# daughter_v2.net
KiCad netlist of a schematic drawn in EAGLE
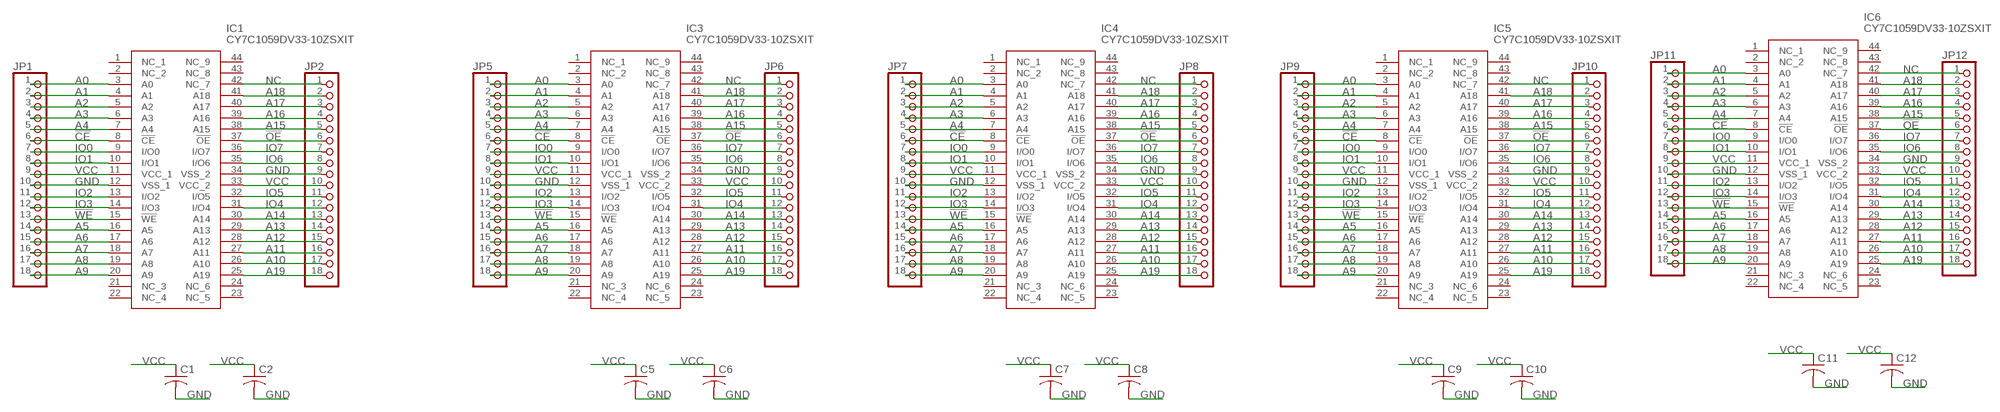
[diagram p0: schematic, sheet 1]

(export (version "E")
  (design (tool "Eeschema 10.0.6"))
  (components
    (comp (ref "C1")
      (value "C-USC0805")
      (footprint "eagle-import:C0805")
      (libsource (lib "eagle-import") (part "C-USC0805"))
    )
    (comp (ref "C2")
      (value "C-USC0805")
      (footprint "eagle-import:C0805")
      (libsource (lib "eagle-import") (part "C-USC0805"))
    )
    (comp (ref "C5")
      (value "C-USC0805")
      (footprint "eagle-import:C0805")
      (libsource (lib "eagle-import") (part "C-USC0805"))
    )
    (comp (ref "C6")
      (value "C-USC0805")
      (footprint "eagle-import:C0805")
      (libsource (lib "eagle-import") (part "C-USC0805"))
    )
    (comp (ref "C7")
      (value "C-USC0805")
      (footprint "eagle-import:C0805")
      (libsource (lib "eagle-import") (part "C-USC0805"))
    )
    (comp (ref "C8")
      (value "C-USC0805")
      (footprint "eagle-import:C0805")
      (libsource (lib "eagle-import") (part "C-USC0805"))
    )
    (comp (ref "C9")
      (value "C-USC0805")
      (footprint "eagle-import:C0805")
      (libsource (lib "eagle-import") (part "C-USC0805"))
    )
    (comp (ref "C10")
      (value "C-USC0805")
      (footprint "eagle-import:C0805")
      (libsource (lib "eagle-import") (part "C-USC0805"))
    )
    (comp (ref "C11")
      (value "C-USC0805")
      (footprint "eagle-import:C0805")
      (libsource (lib "eagle-import") (part "C-USC0805"))
    )
    (comp (ref "C12")
      (value "C-USC0805")
      (footprint "eagle-import:C0805")
      (libsource (lib "eagle-import") (part "C-USC0805"))
    )
    (comp (ref "IC1")
      (value "CY7C1059DV33-10ZSXIT")
      (footprint "eagle-import:SOP80P1184X119-44N")
      (fields (field (name "MOUSER_PART_NUMBER") "727-C1059DV3310ZSXIT"))
      (libsource (lib "eagle-import") (part "CY7C1059DV33-10ZSXIT"))
    )
    (comp (ref "IC3")
      (value "CY7C1059DV33-10ZSXIT")
      (footprint "eagle-import:SOP80P1184X119-44N")
      (fields (field (name "MOUSER_PART_NUMBER") "727-C1059DV3310ZSXIT"))
      (libsource (lib "eagle-import") (part "CY7C1059DV33-10ZSXIT"))
    )
    (comp (ref "IC4")
      (value "CY7C1059DV33-10ZSXIT")
      (footprint "eagle-import:SOP80P1184X119-44N")
      (fields (field (name "MOUSER_PART_NUMBER") "727-C1059DV3310ZSXIT"))
      (libsource (lib "eagle-import") (part "CY7C1059DV33-10ZSXIT"))
    )
    (comp (ref "IC5")
      (value "CY7C1059DV33-10ZSXIT")
      (footprint "eagle-import:SOP80P1184X119-44N")
      (fields (field (name "MOUSER_PART_NUMBER") "727-C1059DV3310ZSXIT"))
      (libsource (lib "eagle-import") (part "CY7C1059DV33-10ZSXIT"))
    )
    (comp (ref "IC6")
      (value "CY7C1059DV33-10ZSXIT")
      (footprint "eagle-import:SOP80P1184X119-44N")
      (fields (field (name "MOUSER_PART_NUMBER") "727-C1059DV3310ZSXIT"))
      (libsource (lib "eagle-import") (part "CY7C1059DV33-10ZSXIT"))
    )
    (comp (ref "JP1")
      (value "PINHD-1X18")
      (footprint "eagle-import:1X18")
      (libsource (lib "eagle-import") (part "PINHD-1X18"))
    )
    (comp (ref "JP2")
      (value "PINHD-1X18")
      (footprint "eagle-import:1X18")
      (libsource (lib "eagle-import") (part "PINHD-1X18"))
    )
    (comp (ref "JP5")
      (value "PINHD-1X18")
      (footprint "eagle-import:1X18")
      (libsource (lib "eagle-import") (part "PINHD-1X18"))
    )
    (comp (ref "JP6")
      (value "PINHD-1X18")
      (footprint "eagle-import:1X18")
      (libsource (lib "eagle-import") (part "PINHD-1X18"))
    )
    (comp (ref "JP7")
      (value "PINHD-1X18")
      (footprint "eagle-import:1X18")
      (libsource (lib "eagle-import") (part "PINHD-1X18"))
    )
    (comp (ref "JP8")
      (value "PINHD-1X18")
      (footprint "eagle-import:1X18")
      (libsource (lib "eagle-import") (part "PINHD-1X18"))
    )
    (comp (ref "JP9")
      (value "PINHD-1X18")
      (footprint "eagle-import:1X18")
      (libsource (lib "eagle-import") (part "PINHD-1X18"))
    )
    (comp (ref "JP10")
      (value "PINHD-1X18")
      (footprint "eagle-import:1X18")
      (libsource (lib "eagle-import") (part "PINHD-1X18"))
    )
    (comp (ref "JP11")
      (value "PINHD-1X18")
      (footprint "eagle-import:1X18")
      (libsource (lib "eagle-import") (part "PINHD-1X18"))
    )
    (comp (ref "JP12")
      (value "PINHD-1X18")
      (footprint "eagle-import:1X18")
      (libsource (lib "eagle-import") (part "PINHD-1X18"))
    )
  )
  (nets
    (net (code "1") (name "/A0") (class "Default")
      (node (ref "IC1") (pin "3") (pinfunction "A0_3") (pintype "bidirectional"))
      (node (ref "IC3") (pin "3") (pinfunction "A0_3") (pintype "bidirectional"))
      (node (ref "IC4") (pin "3") (pinfunction "A0_3") (pintype "bidirectional"))
      (node (ref "IC5") (pin "3") (pinfunction "A0_3") (pintype "bidirectional"))
      (node (ref "IC6") (pin "3") (pinfunction "A0_3") (pintype "bidirectional"))
      (node (ref "JP1") (pin "1") (pinfunction "1_1") (pintype "passive"))
      (node (ref "JP11") (pin "1") (pinfunction "1_1") (pintype "passive"))
      (node (ref "JP5") (pin "1") (pinfunction "1_1") (pintype "passive"))
      (node (ref "JP7") (pin "1") (pinfunction "1_1") (pintype "passive"))
      (node (ref "JP9") (pin "1") (pinfunction "1_1") (pintype "passive"))
    )
    (net (code "2") (name "/A1") (class "Default")
      (node (ref "IC1") (pin "4") (pinfunction "A1_4") (pintype "bidirectional"))
      (node (ref "IC3") (pin "4") (pinfunction "A1_4") (pintype "bidirectional"))
      (node (ref "IC4") (pin "4") (pinfunction "A1_4") (pintype "bidirectional"))
      (node (ref "IC5") (pin "4") (pinfunction "A1_4") (pintype "bidirectional"))
      (node (ref "IC6") (pin "4") (pinfunction "A1_4") (pintype "bidirectional"))
      (node (ref "JP1") (pin "2") (pinfunction "2_2") (pintype "passive"))
      (node (ref "JP11") (pin "2") (pinfunction "2_2") (pintype "passive"))
      (node (ref "JP5") (pin "2") (pinfunction "2_2") (pintype "passive"))
      (node (ref "JP7") (pin "2") (pinfunction "2_2") (pintype "passive"))
      (node (ref "JP9") (pin "2") (pinfunction "2_2") (pintype "passive"))
    )
    (net (code "3") (name "/A2") (class "Default")
      (node (ref "IC1") (pin "5") (pinfunction "A2_5") (pintype "bidirectional"))
      (node (ref "IC3") (pin "5") (pinfunction "A2_5") (pintype "bidirectional"))
      (node (ref "IC4") (pin "5") (pinfunction "A2_5") (pintype "bidirectional"))
      (node (ref "IC5") (pin "5") (pinfunction "A2_5") (pintype "bidirectional"))
      (node (ref "IC6") (pin "5") (pinfunction "A2_5") (pintype "bidirectional"))
      (node (ref "JP1") (pin "3") (pinfunction "3_3") (pintype "passive"))
      (node (ref "JP11") (pin "3") (pinfunction "3_3") (pintype "passive"))
      (node (ref "JP5") (pin "3") (pinfunction "3_3") (pintype "passive"))
      (node (ref "JP7") (pin "3") (pinfunction "3_3") (pintype "passive"))
      (node (ref "JP9") (pin "3") (pinfunction "3_3") (pintype "passive"))
    )
    (net (code "4") (name "/A3") (class "Default")
      (node (ref "IC1") (pin "6") (pinfunction "A3_6") (pintype "bidirectional"))
      (node (ref "IC3") (pin "6") (pinfunction "A3_6") (pintype "bidirectional"))
      (node (ref "IC4") (pin "6") (pinfunction "A3_6") (pintype "bidirectional"))
      (node (ref "IC5") (pin "6") (pinfunction "A3_6") (pintype "bidirectional"))
      (node (ref "IC6") (pin "6") (pinfunction "A3_6") (pintype "bidirectional"))
      (node (ref "JP1") (pin "4") (pinfunction "4_4") (pintype "passive"))
      (node (ref "JP11") (pin "4") (pinfunction "4_4") (pintype "passive"))
      (node (ref "JP5") (pin "4") (pinfunction "4_4") (pintype "passive"))
      (node (ref "JP7") (pin "4") (pinfunction "4_4") (pintype "passive"))
      (node (ref "JP9") (pin "4") (pinfunction "4_4") (pintype "passive"))
    )
    (net (code "5") (name "/A4") (class "Default")
      (node (ref "IC1") (pin "7") (pinfunction "A4_7") (pintype "bidirectional"))
      (node (ref "IC3") (pin "7") (pinfunction "A4_7") (pintype "bidirectional"))
      (node (ref "IC4") (pin "7") (pinfunction "A4_7") (pintype "bidirectional"))
      (node (ref "IC5") (pin "7") (pinfunction "A4_7") (pintype "bidirectional"))
      (node (ref "IC6") (pin "7") (pinfunction "A4_7") (pintype "bidirectional"))
      (node (ref "JP1") (pin "5") (pinfunction "5_5") (pintype "passive"))
      (node (ref "JP11") (pin "5") (pinfunction "5_5") (pintype "passive"))
      (node (ref "JP5") (pin "5") (pinfunction "5_5") (pintype "passive"))
      (node (ref "JP7") (pin "5") (pinfunction "5_5") (pintype "passive"))
      (node (ref "JP9") (pin "5") (pinfunction "5_5") (pintype "passive"))
    )
    (net (code "6") (name "/A5") (class "Default")
      (node (ref "IC1") (pin "16") (pinfunction "A5_16") (pintype "bidirectional"))
      (node (ref "IC3") (pin "16") (pinfunction "A5_16") (pintype "bidirectional"))
      (node (ref "IC4") (pin "16") (pinfunction "A5_16") (pintype "bidirectional"))
      (node (ref "IC5") (pin "16") (pinfunction "A5_16") (pintype "bidirectional"))
      (node (ref "IC6") (pin "16") (pinfunction "A5_16") (pintype "bidirectional"))
      (node (ref "JP1") (pin "14") (pinfunction "14_14") (pintype "passive"))
      (node (ref "JP11") (pin "14") (pinfunction "14_14") (pintype "passive"))
      (node (ref "JP5") (pin "14") (pinfunction "14_14") (pintype "passive"))
      (node (ref "JP7") (pin "14") (pinfunction "14_14") (pintype "passive"))
      (node (ref "JP9") (pin "14") (pinfunction "14_14") (pintype "passive"))
    )
    (net (code "7") (name "/A6") (class "Default")
      (node (ref "IC1") (pin "17") (pinfunction "A6_17") (pintype "bidirectional"))
      (node (ref "IC3") (pin "17") (pinfunction "A6_17") (pintype "bidirectional"))
      (node (ref "IC4") (pin "17") (pinfunction "A6_17") (pintype "bidirectional"))
      (node (ref "IC5") (pin "17") (pinfunction "A6_17") (pintype "bidirectional"))
      (node (ref "IC6") (pin "17") (pinfunction "A6_17") (pintype "bidirectional"))
      (node (ref "JP1") (pin "15") (pinfunction "15_15") (pintype "passive"))
      (node (ref "JP11") (pin "15") (pinfunction "15_15") (pintype "passive"))
      (node (ref "JP5") (pin "15") (pinfunction "15_15") (pintype "passive"))
      (node (ref "JP7") (pin "15") (pinfunction "15_15") (pintype "passive"))
      (node (ref "JP9") (pin "15") (pinfunction "15_15") (pintype "passive"))
    )
    (net (code "8") (name "/A7") (class "Default")
      (node (ref "IC1") (pin "18") (pinfunction "A7_18") (pintype "bidirectional"))
      (node (ref "IC3") (pin "18") (pinfunction "A7_18") (pintype "bidirectional"))
      (node (ref "IC4") (pin "18") (pinfunction "A7_18") (pintype "bidirectional"))
      (node (ref "IC5") (pin "18") (pinfunction "A7_18") (pintype "bidirectional"))
      (node (ref "IC6") (pin "18") (pinfunction "A7_18") (pintype "bidirectional"))
      (node (ref "JP1") (pin "16") (pinfunction "16_16") (pintype "passive"))
      (node (ref "JP11") (pin "16") (pinfunction "16_16") (pintype "passive"))
      (node (ref "JP5") (pin "16") (pinfunction "16_16") (pintype "passive"))
      (node (ref "JP7") (pin "16") (pinfunction "16_16") (pintype "passive"))
      (node (ref "JP9") (pin "16") (pinfunction "16_16") (pintype "passive"))
    )
    (net (code "9") (name "/A8") (class "Default")
      (node (ref "IC1") (pin "19") (pinfunction "A8_19") (pintype "bidirectional"))
      (node (ref "IC3") (pin "19") (pinfunction "A8_19") (pintype "bidirectional"))
      (node (ref "IC4") (pin "19") (pinfunction "A8_19") (pintype "bidirectional"))
      (node (ref "IC5") (pin "19") (pinfunction "A8_19") (pintype "bidirectional"))
      (node (ref "IC6") (pin "19") (pinfunction "A8_19") (pintype "bidirectional"))
      (node (ref "JP1") (pin "17") (pinfunction "17_17") (pintype "passive"))
      (node (ref "JP11") (pin "17") (pinfunction "17_17") (pintype "passive"))
      (node (ref "JP5") (pin "17") (pinfunction "17_17") (pintype "passive"))
      (node (ref "JP7") (pin "17") (pinfunction "17_17") (pintype "passive"))
      (node (ref "JP9") (pin "17") (pinfunction "17_17") (pintype "passive"))
    )
    (net (code "10") (name "/A9") (class "Default")
      (node (ref "IC1") (pin "20") (pinfunction "A9_20") (pintype "bidirectional"))
      (node (ref "IC3") (pin "20") (pinfunction "A9_20") (pintype "bidirectional"))
      (node (ref "IC4") (pin "20") (pinfunction "A9_20") (pintype "bidirectional"))
      (node (ref "IC5") (pin "20") (pinfunction "A9_20") (pintype "bidirectional"))
      (node (ref "IC6") (pin "20") (pinfunction "A9_20") (pintype "bidirectional"))
      (node (ref "JP1") (pin "18") (pinfunction "18_18") (pintype "passive"))
      (node (ref "JP11") (pin "18") (pinfunction "18_18") (pintype "passive"))
      (node (ref "JP5") (pin "18") (pinfunction "18_18") (pintype "passive"))
      (node (ref "JP7") (pin "18") (pinfunction "18_18") (pintype "passive"))
      (node (ref "JP9") (pin "18") (pinfunction "18_18") (pintype "passive"))
    )
    (net (code "11") (name "/A10") (class "Default")
      (node (ref "IC1") (pin "26") (pinfunction "A10_26") (pintype "bidirectional"))
      (node (ref "IC3") (pin "26") (pinfunction "A10_26") (pintype "bidirectional"))
      (node (ref "IC4") (pin "26") (pinfunction "A10_26") (pintype "bidirectional"))
      (node (ref "IC5") (pin "26") (pinfunction "A10_26") (pintype "bidirectional"))
      (node (ref "IC6") (pin "26") (pinfunction "A10_26") (pintype "bidirectional"))
      (node (ref "JP10") (pin "17") (pinfunction "17_17") (pintype "passive"))
      (node (ref "JP12") (pin "17") (pinfunction "17_17") (pintype "passive"))
      (node (ref "JP2") (pin "17") (pinfunction "17_17") (pintype "passive"))
      (node (ref "JP6") (pin "17") (pinfunction "17_17") (pintype "passive"))
      (node (ref "JP8") (pin "17") (pinfunction "17_17") (pintype "passive"))
    )
    (net (code "12") (name "/A11") (class "Default")
      (node (ref "IC1") (pin "27") (pinfunction "A11_27") (pintype "bidirectional"))
      (node (ref "IC3") (pin "27") (pinfunction "A11_27") (pintype "bidirectional"))
      (node (ref "IC4") (pin "27") (pinfunction "A11_27") (pintype "bidirectional"))
      (node (ref "IC5") (pin "27") (pinfunction "A11_27") (pintype "bidirectional"))
      (node (ref "IC6") (pin "27") (pinfunction "A11_27") (pintype "bidirectional"))
      (node (ref "JP10") (pin "16") (pinfunction "16_16") (pintype "passive"))
      (node (ref "JP12") (pin "16") (pinfunction "16_16") (pintype "passive"))
      (node (ref "JP2") (pin "16") (pinfunction "16_16") (pintype "passive"))
      (node (ref "JP6") (pin "16") (pinfunction "16_16") (pintype "passive"))
      (node (ref "JP8") (pin "16") (pinfunction "16_16") (pintype "passive"))
    )
    (net (code "13") (name "/A12") (class "Default")
      (node (ref "IC1") (pin "28") (pinfunction "A12_28") (pintype "bidirectional"))
      (node (ref "IC3") (pin "28") (pinfunction "A12_28") (pintype "bidirectional"))
      (node (ref "IC4") (pin "28") (pinfunction "A12_28") (pintype "bidirectional"))
      (node (ref "IC5") (pin "28") (pinfunction "A12_28") (pintype "bidirectional"))
      (node (ref "IC6") (pin "28") (pinfunction "A12_28") (pintype "bidirectional"))
      (node (ref "JP10") (pin "15") (pinfunction "15_15") (pintype "passive"))
      (node (ref "JP12") (pin "15") (pinfunction "15_15") (pintype "passive"))
      (node (ref "JP2") (pin "15") (pinfunction "15_15") (pintype "passive"))
      (node (ref "JP6") (pin "15") (pinfunction "15_15") (pintype "passive"))
      (node (ref "JP8") (pin "15") (pinfunction "15_15") (pintype "passive"))
    )
    (net (code "14") (name "/A13") (class "Default")
      (node (ref "IC1") (pin "29") (pinfunction "A13_29") (pintype "bidirectional"))
      (node (ref "IC3") (pin "29") (pinfunction "A13_29") (pintype "bidirectional"))
      (node (ref "IC4") (pin "29") (pinfunction "A13_29") (pintype "bidirectional"))
      (node (ref "IC5") (pin "29") (pinfunction "A13_29") (pintype "bidirectional"))
      (node (ref "IC6") (pin "29") (pinfunction "A13_29") (pintype "bidirectional"))
      (node (ref "JP10") (pin "14") (pinfunction "14_14") (pintype "passive"))
      (node (ref "JP12") (pin "14") (pinfunction "14_14") (pintype "passive"))
      (node (ref "JP2") (pin "14") (pinfunction "14_14") (pintype "passive"))
      (node (ref "JP6") (pin "14") (pinfunction "14_14") (pintype "passive"))
      (node (ref "JP8") (pin "14") (pinfunction "14_14") (pintype "passive"))
    )
    (net (code "15") (name "/A14") (class "Default")
      (node (ref "IC1") (pin "30") (pinfunction "A14_30") (pintype "bidirectional"))
      (node (ref "IC3") (pin "30") (pinfunction "A14_30") (pintype "bidirectional"))
      (node (ref "IC4") (pin "30") (pinfunction "A14_30") (pintype "bidirectional"))
      (node (ref "IC5") (pin "30") (pinfunction "A14_30") (pintype "bidirectional"))
      (node (ref "IC6") (pin "30") (pinfunction "A14_30") (pintype "bidirectional"))
      (node (ref "JP10") (pin "13") (pinfunction "13_13") (pintype "passive"))
      (node (ref "JP12") (pin "13") (pinfunction "13_13") (pintype "passive"))
      (node (ref "JP2") (pin "13") (pinfunction "13_13") (pintype "passive"))
      (node (ref "JP6") (pin "13") (pinfunction "13_13") (pintype "passive"))
      (node (ref "JP8") (pin "13") (pinfunction "13_13") (pintype "passive"))
    )
    (net (code "16") (name "/A15") (class "Default")
      (node (ref "IC1") (pin "38") (pinfunction "A15_38") (pintype "bidirectional"))
      (node (ref "IC3") (pin "38") (pinfunction "A15_38") (pintype "bidirectional"))
      (node (ref "IC4") (pin "38") (pinfunction "A15_38") (pintype "bidirectional"))
      (node (ref "IC5") (pin "38") (pinfunction "A15_38") (pintype "bidirectional"))
      (node (ref "IC6") (pin "38") (pinfunction "A15_38") (pintype "bidirectional"))
      (node (ref "JP10") (pin "5") (pinfunction "5_5") (pintype "passive"))
      (node (ref "JP12") (pin "5") (pinfunction "5_5") (pintype "passive"))
      (node (ref "JP2") (pin "5") (pinfunction "5_5") (pintype "passive"))
      (node (ref "JP6") (pin "5") (pinfunction "5_5") (pintype "passive"))
      (node (ref "JP8") (pin "5") (pinfunction "5_5") (pintype "passive"))
    )
    (net (code "17") (name "/A16") (class "Default")
      (node (ref "IC1") (pin "39") (pinfunction "A16_39") (pintype "bidirectional"))
      (node (ref "IC3") (pin "39") (pinfunction "A16_39") (pintype "bidirectional"))
      (node (ref "IC4") (pin "39") (pinfunction "A16_39") (pintype "bidirectional"))
      (node (ref "IC5") (pin "39") (pinfunction "A16_39") (pintype "bidirectional"))
      (node (ref "IC6") (pin "39") (pinfunction "A16_39") (pintype "bidirectional"))
      (node (ref "JP10") (pin "4") (pinfunction "4_4") (pintype "passive"))
      (node (ref "JP12") (pin "4") (pinfunction "4_4") (pintype "passive"))
      (node (ref "JP2") (pin "4") (pinfunction "4_4") (pintype "passive"))
      (node (ref "JP6") (pin "4") (pinfunction "4_4") (pintype "passive"))
      (node (ref "JP8") (pin "4") (pinfunction "4_4") (pintype "passive"))
    )
    (net (code "18") (name "/A17") (class "Default")
      (node (ref "IC1") (pin "40") (pinfunction "A17_40") (pintype "bidirectional"))
      (node (ref "IC3") (pin "40") (pinfunction "A17_40") (pintype "bidirectional"))
      (node (ref "IC4") (pin "40") (pinfunction "A17_40") (pintype "bidirectional"))
      (node (ref "IC5") (pin "40") (pinfunction "A17_40") (pintype "bidirectional"))
      (node (ref "IC6") (pin "40") (pinfunction "A17_40") (pintype "bidirectional"))
      (node (ref "JP10") (pin "3") (pinfunction "3_3") (pintype "passive"))
      (node (ref "JP12") (pin "3") (pinfunction "3_3") (pintype "passive"))
      (node (ref "JP2") (pin "3") (pinfunction "3_3") (pintype "passive"))
      (node (ref "JP6") (pin "3") (pinfunction "3_3") (pintype "passive"))
      (node (ref "JP8") (pin "3") (pinfunction "3_3") (pintype "passive"))
    )
    (net (code "19") (name "/A18") (class "Default")
      (node (ref "IC1") (pin "41") (pinfunction "A18_41") (pintype "bidirectional"))
      (node (ref "IC3") (pin "41") (pinfunction "A18_41") (pintype "bidirectional"))
      (node (ref "IC4") (pin "41") (pinfunction "A18_41") (pintype "bidirectional"))
      (node (ref "IC5") (pin "41") (pinfunction "A18_41") (pintype "bidirectional"))
      (node (ref "IC6") (pin "41") (pinfunction "A18_41") (pintype "bidirectional"))
      (node (ref "JP10") (pin "2") (pinfunction "2_2") (pintype "passive"))
      (node (ref "JP12") (pin "2") (pinfunction "2_2") (pintype "passive"))
      (node (ref "JP2") (pin "2") (pinfunction "2_2") (pintype "passive"))
      (node (ref "JP6") (pin "2") (pinfunction "2_2") (pintype "passive"))
      (node (ref "JP8") (pin "2") (pinfunction "2_2") (pintype "passive"))
    )
    (net (code "20") (name "/A19") (class "Default")
      (node (ref "IC1") (pin "25") (pinfunction "A19_25") (pintype "bidirectional"))
      (node (ref "IC3") (pin "25") (pinfunction "A19_25") (pintype "bidirectional"))
      (node (ref "IC4") (pin "25") (pinfunction "A19_25") (pintype "bidirectional"))
      (node (ref "IC5") (pin "25") (pinfunction "A19_25") (pintype "bidirectional"))
      (node (ref "IC6") (pin "25") (pinfunction "A19_25") (pintype "bidirectional"))
      (node (ref "JP10") (pin "18") (pinfunction "18_18") (pintype "passive"))
      (node (ref "JP12") (pin "18") (pinfunction "18_18") (pintype "passive"))
      (node (ref "JP2") (pin "18") (pinfunction "18_18") (pintype "passive"))
      (node (ref "JP6") (pin "18") (pinfunction "18_18") (pintype "passive"))
      (node (ref "JP8") (pin "18") (pinfunction "18_18") (pintype "passive"))
    )
    (net (code "21") (name "/GND") (class "Default")
      (node (ref "C1") (pin "2") (pinfunction "2_2") (pintype "passive"))
      (node (ref "C10") (pin "2") (pinfunction "2_2") (pintype "passive"))
      (node (ref "C11") (pin "2") (pinfunction "2_2") (pintype "passive"))
      (node (ref "C12") (pin "2") (pinfunction "2_2") (pintype "passive"))
      (node (ref "C2") (pin "2") (pinfunction "2_2") (pintype "passive"))
      (node (ref "C5") (pin "2") (pinfunction "2_2") (pintype "passive"))
      (node (ref "C6") (pin "2") (pinfunction "2_2") (pintype "passive"))
      (node (ref "C7") (pin "2") (pinfunction "2_2") (pintype "passive"))
      (node (ref "C8") (pin "2") (pinfunction "2_2") (pintype "passive"))
      (node (ref "C9") (pin "2") (pinfunction "2_2") (pintype "passive"))
      (node (ref "IC1") (pin "12") (pinfunction "VSS_1_12") (pintype "bidirectional"))
      (node (ref "IC1") (pin "34") (pinfunction "VSS_2_34") (pintype "bidirectional"))
      (node (ref "IC3") (pin "12") (pinfunction "VSS_1_12") (pintype "bidirectional"))
      (node (ref "IC3") (pin "34") (pinfunction "VSS_2_34") (pintype "bidirectional"))
      (node (ref "IC4") (pin "12") (pinfunction "VSS_1_12") (pintype "bidirectional"))
      (node (ref "IC4") (pin "34") (pinfunction "VSS_2_34") (pintype "bidirectional"))
      (node (ref "IC5") (pin "12") (pinfunction "VSS_1_12") (pintype "bidirectional"))
      (node (ref "IC5") (pin "34") (pinfunction "VSS_2_34") (pintype "bidirectional"))
      (node (ref "IC6") (pin "12") (pinfunction "VSS_1_12") (pintype "bidirectional"))
      (node (ref "IC6") (pin "34") (pinfunction "VSS_2_34") (pintype "bidirectional"))
      (node (ref "JP1") (pin "10") (pinfunction "10_10") (pintype "passive"))
      (node (ref "JP10") (pin "9") (pinfunction "9_9") (pintype "passive"))
      (node (ref "JP11") (pin "10") (pinfunction "10_10") (pintype "passive"))
      (node (ref "JP12") (pin "9") (pinfunction "9_9") (pintype "passive"))
      (node (ref "JP2") (pin "9") (pinfunction "9_9") (pintype "passive"))
      (node (ref "JP5") (pin "10") (pinfunction "10_10") (pintype "passive"))
      (node (ref "JP6") (pin "9") (pinfunction "9_9") (pintype "passive"))
      (node (ref "JP7") (pin "10") (pinfunction "10_10") (pintype "passive"))
      (node (ref "JP8") (pin "9") (pinfunction "9_9") (pintype "passive"))
      (node (ref "JP9") (pin "10") (pinfunction "10_10") (pintype "passive"))
    )
    (net (code "22") (name "/IO0") (class "Default")
      (node (ref "IC1") (pin "9") (pinfunction "I/O0_9") (pintype "bidirectional"))
      (node (ref "IC3") (pin "9") (pinfunction "I/O0_9") (pintype "bidirectional"))
      (node (ref "IC4") (pin "9") (pinfunction "I/O0_9") (pintype "bidirectional"))
      (node (ref "IC5") (pin "9") (pinfunction "I/O0_9") (pintype "bidirectional"))
      (node (ref "IC6") (pin "9") (pinfunction "I/O0_9") (pintype "bidirectional"))
      (node (ref "JP1") (pin "7") (pinfunction "7_7") (pintype "passive"))
      (node (ref "JP11") (pin "7") (pinfunction "7_7") (pintype "passive"))
      (node (ref "JP5") (pin "7") (pinfunction "7_7") (pintype "passive"))
      (node (ref "JP7") (pin "7") (pinfunction "7_7") (pintype "passive"))
      (node (ref "JP9") (pin "7") (pinfunction "7_7") (pintype "passive"))
    )
    (net (code "23") (name "/IO1") (class "Default")
      (node (ref "IC1") (pin "10") (pinfunction "I/O1_10") (pintype "bidirectional"))
      (node (ref "IC3") (pin "10") (pinfunction "I/O1_10") (pintype "bidirectional"))
      (node (ref "IC4") (pin "10") (pinfunction "I/O1_10") (pintype "bidirectional"))
      (node (ref "IC5") (pin "10") (pinfunction "I/O1_10") (pintype "bidirectional"))
      (node (ref "IC6") (pin "10") (pinfunction "I/O1_10") (pintype "bidirectional"))
      (node (ref "JP1") (pin "8") (pinfunction "8_8") (pintype "passive"))
      (node (ref "JP11") (pin "8") (pinfunction "8_8") (pintype "passive"))
      (node (ref "JP5") (pin "8") (pinfunction "8_8") (pintype "passive"))
      (node (ref "JP7") (pin "8") (pinfunction "8_8") (pintype "passive"))
      (node (ref "JP9") (pin "8") (pinfunction "8_8") (pintype "passive"))
    )
    (net (code "24") (name "/IO2") (class "Default")
      (node (ref "IC1") (pin "13") (pinfunction "I/O2_13") (pintype "bidirectional"))
      (node (ref "IC3") (pin "13") (pinfunction "I/O2_13") (pintype "bidirectional"))
      (node (ref "IC4") (pin "13") (pinfunction "I/O2_13") (pintype "bidirectional"))
      (node (ref "IC5") (pin "13") (pinfunction "I/O2_13") (pintype "bidirectional"))
      (node (ref "IC6") (pin "13") (pinfunction "I/O2_13") (pintype "bidirectional"))
      (node (ref "JP1") (pin "11") (pinfunction "11_11") (pintype "passive"))
      (node (ref "JP11") (pin "11") (pinfunction "11_11") (pintype "passive"))
      (node (ref "JP5") (pin "11") (pinfunction "11_11") (pintype "passive"))
      (node (ref "JP7") (pin "11") (pinfunction "11_11") (pintype "passive"))
      (node (ref "JP9") (pin "11") (pinfunction "11_11") (pintype "passive"))
    )
    (net (code "25") (name "/IO3") (class "Default")
      (node (ref "IC1") (pin "14") (pinfunction "I/O3_14") (pintype "bidirectional"))
      (node (ref "IC3") (pin "14") (pinfunction "I/O3_14") (pintype "bidirectional"))
      (node (ref "IC4") (pin "14") (pinfunction "I/O3_14") (pintype "bidirectional"))
      (node (ref "IC5") (pin "14") (pinfunction "I/O3_14") (pintype "bidirectional"))
      (node (ref "IC6") (pin "14") (pinfunction "I/O3_14") (pintype "bidirectional"))
      (node (ref "JP1") (pin "12") (pinfunction "12_12") (pintype "passive"))
      (node (ref "JP11") (pin "12") (pinfunction "12_12") (pintype "passive"))
      (node (ref "JP5") (pin "12") (pinfunction "12_12") (pintype "passive"))
      (node (ref "JP7") (pin "12") (pinfunction "12_12") (pintype "passive"))
      (node (ref "JP9") (pin "12") (pinfunction "12_12") (pintype "passive"))
    )
    (net (code "26") (name "/IO4") (class "Default")
      (node (ref "IC1") (pin "31") (pinfunction "I/O4_31") (pintype "bidirectional"))
      (node (ref "IC3") (pin "31") (pinfunction "I/O4_31") (pintype "bidirectional"))
      (node (ref "IC4") (pin "31") (pinfunction "I/O4_31") (pintype "bidirectional"))
      (node (ref "IC5") (pin "31") (pinfunction "I/O4_31") (pintype "bidirectional"))
      (node (ref "IC6") (pin "31") (pinfunction "I/O4_31") (pintype "bidirectional"))
      (node (ref "JP10") (pin "12") (pinfunction "12_12") (pintype "passive"))
      (node (ref "JP12") (pin "12") (pinfunction "12_12") (pintype "passive"))
      (node (ref "JP2") (pin "12") (pinfunction "12_12") (pintype "passive"))
      (node (ref "JP6") (pin "12") (pinfunction "12_12") (pintype "passive"))
      (node (ref "JP8") (pin "12") (pinfunction "12_12") (pintype "passive"))
    )
    (net (code "27") (name "/IO5") (class "Default")
      (node (ref "IC1") (pin "32") (pinfunction "I/O5_32") (pintype "bidirectional"))
      (node (ref "IC3") (pin "32") (pinfunction "I/O5_32") (pintype "bidirectional"))
      (node (ref "IC4") (pin "32") (pinfunction "I/O5_32") (pintype "bidirectional"))
      (node (ref "IC5") (pin "32") (pinfunction "I/O5_32") (pintype "bidirectional"))
      (node (ref "IC6") (pin "32") (pinfunction "I/O5_32") (pintype "bidirectional"))
      (node (ref "JP10") (pin "11") (pinfunction "11_11") (pintype "passive"))
      (node (ref "JP12") (pin "11") (pinfunction "11_11") (pintype "passive"))
      (node (ref "JP2") (pin "11") (pinfunction "11_11") (pintype "passive"))
      (node (ref "JP6") (pin "11") (pinfunction "11_11") (pintype "passive"))
      (node (ref "JP8") (pin "11") (pinfunction "11_11") (pintype "passive"))
    )
    (net (code "28") (name "/IO6") (class "Default")
      (node (ref "IC1") (pin "35") (pinfunction "I/O6_35") (pintype "bidirectional"))
      (node (ref "IC3") (pin "35") (pinfunction "I/O6_35") (pintype "bidirectional"))
      (node (ref "IC4") (pin "35") (pinfunction "I/O6_35") (pintype "bidirectional"))
      (node (ref "IC5") (pin "35") (pinfunction "I/O6_35") (pintype "bidirectional"))
      (node (ref "IC6") (pin "35") (pinfunction "I/O6_35") (pintype "bidirectional"))
      (node (ref "JP10") (pin "8") (pinfunction "8_8") (pintype "passive"))
      (node (ref "JP12") (pin "8") (pinfunction "8_8") (pintype "passive"))
      (node (ref "JP2") (pin "8") (pinfunction "8_8") (pintype "passive"))
      (node (ref "JP6") (pin "8") (pinfunction "8_8") (pintype "passive"))
      (node (ref "JP8") (pin "8") (pinfunction "8_8") (pintype "passive"))
    )
    (net (code "29") (name "/IO7") (class "Default")
      (node (ref "IC1") (pin "36") (pinfunction "I/O7_36") (pintype "bidirectional"))
      (node (ref "IC3") (pin "36") (pinfunction "I/O7_36") (pintype "bidirectional"))
      (node (ref "IC4") (pin "36") (pinfunction "I/O7_36") (pintype "bidirectional"))
      (node (ref "IC5") (pin "36") (pinfunction "I/O7_36") (pintype "bidirectional"))
      (node (ref "IC6") (pin "36") (pinfunction "I/O7_36") (pintype "bidirectional"))
      (node (ref "JP10") (pin "7") (pinfunction "7_7") (pintype "passive"))
      (node (ref "JP12") (pin "7") (pinfunction "7_7") (pintype "passive"))
      (node (ref "JP2") (pin "7") (pinfunction "7_7") (pintype "passive"))
      (node (ref "JP6") (pin "7") (pinfunction "7_7") (pintype "passive"))
      (node (ref "JP8") (pin "7") (pinfunction "7_7") (pintype "passive"))
    )
    (net (code "30") (name "/NC") (class "Default")
      (node (ref "IC1") (pin "42") (pinfunction "NC_7_42") (pintype "bidirectional"))
      (node (ref "IC3") (pin "42") (pinfunction "NC_7_42") (pintype "bidirectional"))
      (node (ref "IC4") (pin "42") (pinfunction "NC_7_42") (pintype "bidirectional"))
      (node (ref "IC5") (pin "42") (pinfunction "NC_7_42") (pintype "bidirectional"))
      (node (ref "IC6") (pin "42") (pinfunction "NC_7_42") (pintype "bidirectional"))
      (node (ref "JP10") (pin "1") (pinfunction "1_1") (pintype "passive"))
      (node (ref "JP12") (pin "1") (pinfunction "1_1") (pintype "passive"))
      (node (ref "JP2") (pin "1") (pinfunction "1_1") (pintype "passive"))
      (node (ref "JP6") (pin "1") (pinfunction "1_1") (pintype "passive"))
      (node (ref "JP8") (pin "1") (pinfunction "1_1") (pintype "passive"))
    )
    (net (code "31") (name "/VCC") (class "Default")
      (node (ref "C1") (pin "1") (pinfunction "1_1") (pintype "passive"))
      (node (ref "C10") (pin "1") (pinfunction "1_1") (pintype "passive"))
      (node (ref "C11") (pin "1") (pinfunction "1_1") (pintype "passive"))
      (node (ref "C12") (pin "1") (pinfunction "1_1") (pintype "passive"))
      (node (ref "C2") (pin "1") (pinfunction "1_1") (pintype "passive"))
      (node (ref "C5") (pin "1") (pinfunction "1_1") (pintype "passive"))
      (node (ref "C6") (pin "1") (pinfunction "1_1") (pintype "passive"))
      (node (ref "C7") (pin "1") (pinfunction "1_1") (pintype "passive"))
      (node (ref "C8") (pin "1") (pinfunction "1_1") (pintype "passive"))
      (node (ref "C9") (pin "1") (pinfunction "1_1") (pintype "passive"))
      (node (ref "IC1") (pin "11") (pinfunction "VCC_1_11") (pintype "bidirectional"))
      (node (ref "IC1") (pin "33") (pinfunction "VCC_2_33") (pintype "bidirectional"))
      (node (ref "IC3") (pin "11") (pinfunction "VCC_1_11") (pintype "bidirectional"))
      (node (ref "IC3") (pin "33") (pinfunction "VCC_2_33") (pintype "bidirectional"))
      (node (ref "IC4") (pin "11") (pinfunction "VCC_1_11") (pintype "bidirectional"))
      (node (ref "IC4") (pin "33") (pinfunction "VCC_2_33") (pintype "bidirectional"))
      (node (ref "IC5") (pin "11") (pinfunction "VCC_1_11") (pintype "bidirectional"))
      (node (ref "IC5") (pin "33") (pinfunction "VCC_2_33") (pintype "bidirectional"))
      (node (ref "IC6") (pin "11") (pinfunction "VCC_1_11") (pintype "bidirectional"))
      (node (ref "IC6") (pin "33") (pinfunction "VCC_2_33") (pintype "bidirectional"))
      (node (ref "JP1") (pin "9") (pinfunction "9_9") (pintype "passive"))
      (node (ref "JP10") (pin "10") (pinfunction "10_10") (pintype "passive"))
      (node (ref "JP11") (pin "9") (pinfunction "9_9") (pintype "passive"))
      (node (ref "JP12") (pin "10") (pinfunction "10_10") (pintype "passive"))
      (node (ref "JP2") (pin "10") (pinfunction "10_10") (pintype "passive"))
      (node (ref "JP5") (pin "9") (pinfunction "9_9") (pintype "passive"))
      (node (ref "JP6") (pin "10") (pinfunction "10_10") (pintype "passive"))
      (node (ref "JP7") (pin "9") (pinfunction "9_9") (pintype "passive"))
      (node (ref "JP8") (pin "10") (pinfunction "10_10") (pintype "passive"))
      (node (ref "JP9") (pin "9") (pinfunction "9_9") (pintype "passive"))
    )
    (net (code "32") (name "/~{CE}") (class "Default")
      (node (ref "IC1") (pin "8") (pinfunction "~{CE}_8") (pintype "bidirectional"))
      (node (ref "IC3") (pin "8") (pinfunction "~{CE}_8") (pintype "bidirectional"))
      (node (ref "IC4") (pin "8") (pinfunction "~{CE}_8") (pintype "bidirectional"))
      (node (ref "IC5") (pin "8") (pinfunction "~{CE}_8") (pintype "bidirectional"))
      (node (ref "IC6") (pin "8") (pinfunction "~{CE}_8") (pintype "bidirectional"))
      (node (ref "JP1") (pin "6") (pinfunction "6_6") (pintype "passive"))
      (node (ref "JP11") (pin "6") (pinfunction "6_6") (pintype "passive"))
      (node (ref "JP5") (pin "6") (pinfunction "6_6") (pintype "passive"))
      (node (ref "JP7") (pin "6") (pinfunction "6_6") (pintype "passive"))
      (node (ref "JP9") (pin "6") (pinfunction "6_6") (pintype "passive"))
    )
    (net (code "33") (name "/~{OE}") (class "Default")
      (node (ref "IC1") (pin "37") (pinfunction "~{OE}_37") (pintype "bidirectional"))
      (node (ref "IC3") (pin "37") (pinfunction "~{OE}_37") (pintype "bidirectional"))
      (node (ref "IC4") (pin "37") (pinfunction "~{OE}_37") (pintype "bidirectional"))
      (node (ref "IC5") (pin "37") (pinfunction "~{OE}_37") (pintype "bidirectional"))
      (node (ref "IC6") (pin "37") (pinfunction "~{OE}_37") (pintype "bidirectional"))
      (node (ref "JP10") (pin "6") (pinfunction "6_6") (pintype "passive"))
      (node (ref "JP12") (pin "6") (pinfunction "6_6") (pintype "passive"))
      (node (ref "JP2") (pin "6") (pinfunction "6_6") (pintype "passive"))
      (node (ref "JP6") (pin "6") (pinfunction "6_6") (pintype "passive"))
      (node (ref "JP8") (pin "6") (pinfunction "6_6") (pintype "passive"))
    )
    (net (code "34") (name "/~{WE}") (class "Default")
      (node (ref "IC1") (pin "15") (pinfunction "~{WE}_15") (pintype "bidirectional"))
      (node (ref "IC3") (pin "15") (pinfunction "~{WE}_15") (pintype "bidirectional"))
      (node (ref "IC4") (pin "15") (pinfunction "~{WE}_15") (pintype "bidirectional"))
      (node (ref "IC5") (pin "15") (pinfunction "~{WE}_15") (pintype "bidirectional"))
      (node (ref "IC6") (pin "15") (pinfunction "~{WE}_15") (pintype "bidirectional"))
      (node (ref "JP1") (pin "13") (pinfunction "13_13") (pintype "passive"))
      (node (ref "JP11") (pin "13") (pinfunction "13_13") (pintype "passive"))
      (node (ref "JP5") (pin "13") (pinfunction "13_13") (pintype "passive"))
      (node (ref "JP7") (pin "13") (pinfunction "13_13") (pintype "passive"))
      (node (ref "JP9") (pin "13") (pinfunction "13_13") (pintype "passive"))
    )
    (net (code "35") (name "unconnected-(IC1-NC_1-Pad1)") (class "Default")
      (node (ref "IC1") (pin "1") (pinfunction "NC_1_1") (pintype "bidirectional"))
    )
    (net (code "36") (name "unconnected-(IC1-NC_2-Pad2)") (class "Default")
      (node (ref "IC1") (pin "2") (pinfunction "NC_2_2") (pintype "bidirectional"))
    )
    (net (code "37") (name "unconnected-(IC1-NC_3-Pad21)") (class "Default")
      (node (ref "IC1") (pin "21") (pinfunction "NC_3_21") (pintype "bidirectional"))
    )
    (net (code "38") (name "unconnected-(IC1-NC_4-Pad22)") (class "Default")
      (node (ref "IC1") (pin "22") (pinfunction "NC_4_22") (pintype "bidirectional"))
    )
    (net (code "39") (name "unconnected-(IC1-NC_5-Pad23)") (class "Default")
      (node (ref "IC1") (pin "23") (pinfunction "NC_5_23") (pintype "bidirectional"))
    )
    (net (code "40") (name "unconnected-(IC1-NC_6-Pad24)") (class "Default")
      (node (ref "IC1") (pin "24") (pinfunction "NC_6_24") (pintype "bidirectional"))
    )
    (net (code "41") (name "unconnected-(IC1-NC_8-Pad43)") (class "Default")
      (node (ref "IC1") (pin "43") (pinfunction "NC_8_43") (pintype "bidirectional"))
    )
    (net (code "42") (name "unconnected-(IC1-NC_9-Pad44)") (class "Default")
      (node (ref "IC1") (pin "44") (pinfunction "NC_9_44") (pintype "bidirectional"))
    )
    (net (code "43") (name "unconnected-(IC3-NC_1-Pad1)") (class "Default")
      (node (ref "IC3") (pin "1") (pinfunction "NC_1_1") (pintype "bidirectional"))
    )
    (net (code "44") (name "unconnected-(IC3-NC_2-Pad2)") (class "Default")
      (node (ref "IC3") (pin "2") (pinfunction "NC_2_2") (pintype "bidirectional"))
    )
    (net (code "45") (name "unconnected-(IC3-NC_3-Pad21)") (class "Default")
      (node (ref "IC3") (pin "21") (pinfunction "NC_3_21") (pintype "bidirectional"))
    )
    (net (code "46") (name "unconnected-(IC3-NC_4-Pad22)") (class "Default")
      (node (ref "IC3") (pin "22") (pinfunction "NC_4_22") (pintype "bidirectional"))
    )
    (net (code "47") (name "unconnected-(IC3-NC_5-Pad23)") (class "Default")
      (node (ref "IC3") (pin "23") (pinfunction "NC_5_23") (pintype "bidirectional"))
    )
    (net (code "48") (name "unconnected-(IC3-NC_6-Pad24)") (class "Default")
      (node (ref "IC3") (pin "24") (pinfunction "NC_6_24") (pintype "bidirectional"))
    )
    (net (code "49") (name "unconnected-(IC3-NC_8-Pad43)") (class "Default")
      (node (ref "IC3") (pin "43") (pinfunction "NC_8_43") (pintype "bidirectional"))
    )
    (net (code "50") (name "unconnected-(IC3-NC_9-Pad44)") (class "Default")
      (node (ref "IC3") (pin "44") (pinfunction "NC_9_44") (pintype "bidirectional"))
    )
    (net (code "51") (name "unconnected-(IC4-NC_1-Pad1)") (class "Default")
      (node (ref "IC4") (pin "1") (pinfunction "NC_1_1") (pintype "bidirectional"))
    )
    (net (code "52") (name "unconnected-(IC4-NC_2-Pad2)") (class "Default")
      (node (ref "IC4") (pin "2") (pinfunction "NC_2_2") (pintype "bidirectional"))
    )
    (net (code "53") (name "unconnected-(IC4-NC_3-Pad21)") (class "Default")
      (node (ref "IC4") (pin "21") (pinfunction "NC_3_21") (pintype "bidirectional"))
    )
    (net (code "54") (name "unconnected-(IC4-NC_4-Pad22)") (class "Default")
      (node (ref "IC4") (pin "22") (pinfunction "NC_4_22") (pintype "bidirectional"))
    )
    (net (code "55") (name "unconnected-(IC4-NC_5-Pad23)") (class "Default")
      (node (ref "IC4") (pin "23") (pinfunction "NC_5_23") (pintype "bidirectional"))
    )
    (net (code "56") (name "unconnected-(IC4-NC_6-Pad24)") (class "Default")
      (node (ref "IC4") (pin "24") (pinfunction "NC_6_24") (pintype "bidirectional"))
    )
    (net (code "57") (name "unconnected-(IC4-NC_8-Pad43)") (class "Default")
      (node (ref "IC4") (pin "43") (pinfunction "NC_8_43") (pintype "bidirectional"))
    )
    (net (code "58") (name "unconnected-(IC4-NC_9-Pad44)") (class "Default")
      (node (ref "IC4") (pin "44") (pinfunction "NC_9_44") (pintype "bidirectional"))
    )
    (net (code "59") (name "unconnected-(IC5-NC_1-Pad1)") (class "Default")
      (node (ref "IC5") (pin "1") (pinfunction "NC_1_1") (pintype "bidirectional"))
    )
    (net (code "60") (name "unconnected-(IC5-NC_2-Pad2)") (class "Default")
      (node (ref "IC5") (pin "2") (pinfunction "NC_2_2") (pintype "bidirectional"))
    )
    (net (code "61") (name "unconnected-(IC5-NC_3-Pad21)") (class "Default")
      (node (ref "IC5") (pin "21") (pinfunction "NC_3_21") (pintype "bidirectional"))
    )
    (net (code "62") (name "unconnected-(IC5-NC_4-Pad22)") (class "Default")
      (node (ref "IC5") (pin "22") (pinfunction "NC_4_22") (pintype "bidirectional"))
    )
    (net (code "63") (name "unconnected-(IC5-NC_5-Pad23)") (class "Default")
      (node (ref "IC5") (pin "23") (pinfunction "NC_5_23") (pintype "bidirectional"))
    )
    (net (code "64") (name "unconnected-(IC5-NC_6-Pad24)") (class "Default")
      (node (ref "IC5") (pin "24") (pinfunction "NC_6_24") (pintype "bidirectional"))
    )
    (net (code "65") (name "unconnected-(IC5-NC_8-Pad43)") (class "Default")
      (node (ref "IC5") (pin "43") (pinfunction "NC_8_43") (pintype "bidirectional"))
    )
    (net (code "66") (name "unconnected-(IC5-NC_9-Pad44)") (class "Default")
      (node (ref "IC5") (pin "44") (pinfunction "NC_9_44") (pintype "bidirectional"))
    )
    (net (code "67") (name "unconnected-(IC6-NC_1-Pad1)") (class "Default")
      (node (ref "IC6") (pin "1") (pinfunction "NC_1_1") (pintype "bidirectional"))
    )
    (net (code "68") (name "unconnected-(IC6-NC_2-Pad2)") (class "Default")
      (node (ref "IC6") (pin "2") (pinfunction "NC_2_2") (pintype "bidirectional"))
    )
    (net (code "69") (name "unconnected-(IC6-NC_3-Pad21)") (class "Default")
      (node (ref "IC6") (pin "21") (pinfunction "NC_3_21") (pintype "bidirectional"))
    )
    (net (code "70") (name "unconnected-(IC6-NC_4-Pad22)") (class "Default")
      (node (ref "IC6") (pin "22") (pinfunction "NC_4_22") (pintype "bidirectional"))
    )
    (net (code "71") (name "unconnected-(IC6-NC_5-Pad23)") (class "Default")
      (node (ref "IC6") (pin "23") (pinfunction "NC_5_23") (pintype "bidirectional"))
    )
    (net (code "72") (name "unconnected-(IC6-NC_6-Pad24)") (class "Default")
      (node (ref "IC6") (pin "24") (pinfunction "NC_6_24") (pintype "bidirectional"))
    )
    (net (code "73") (name "unconnected-(IC6-NC_8-Pad43)") (class "Default")
      (node (ref "IC6") (pin "43") (pinfunction "NC_8_43") (pintype "bidirectional"))
    )
    (net (code "74") (name "unconnected-(IC6-NC_9-Pad44)") (class "Default")
      (node (ref "IC6") (pin "44") (pinfunction "NC_9_44") (pintype "bidirectional"))
    )
  )
)
